# L298213.net
KiCad netlist of a schematic drawn in EAGLE
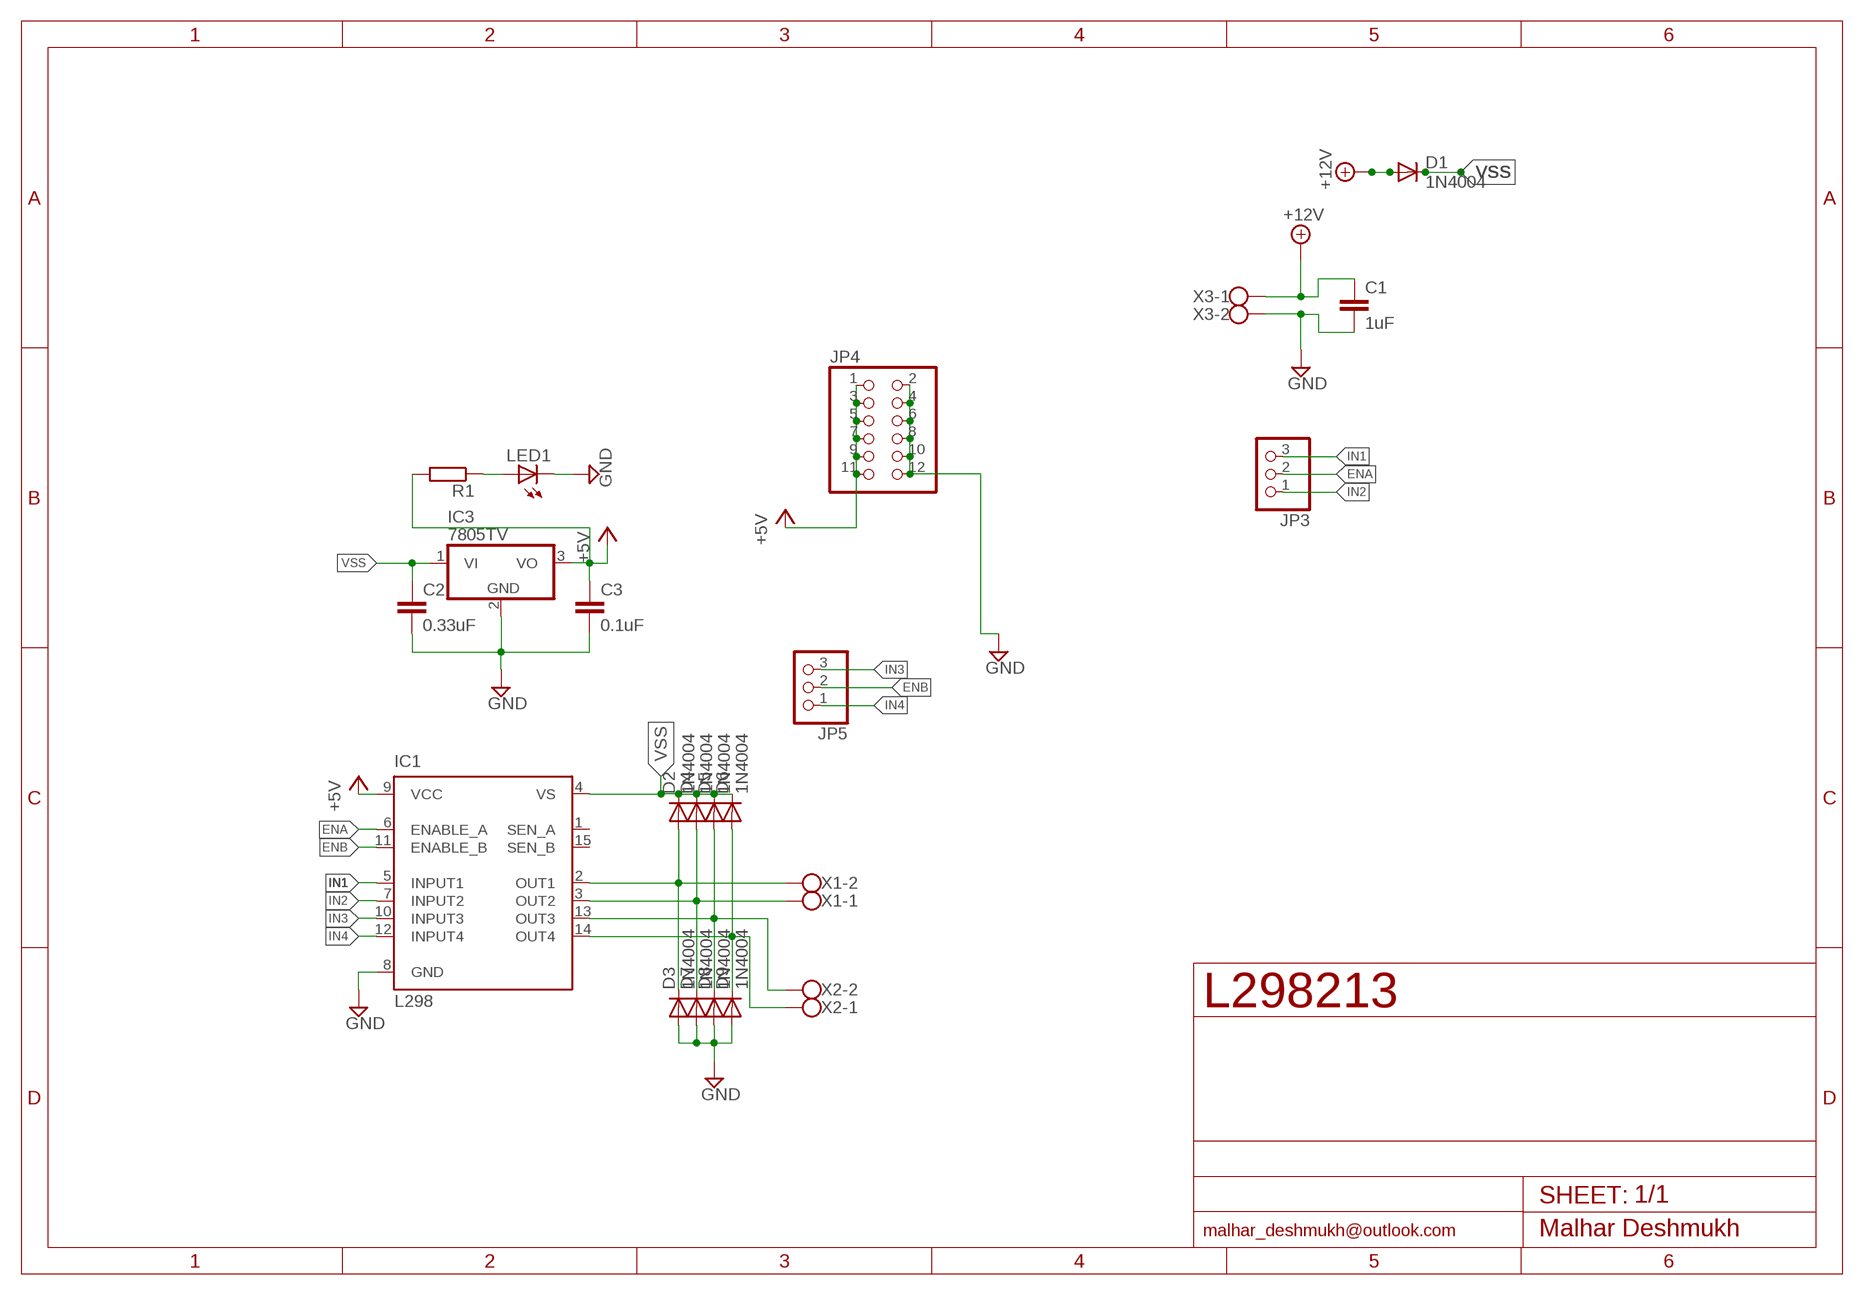
[diagram p0: schematic, sheet 1]

(export (version "E")
  (design (tool "Eeschema 10.0.6"))
  (components
    (comp (ref "C1")
      (value "1uF")
      (footprint "eagle-import:C050-024X044")
      (libsource (lib "eagle-import") (part "C-EU050-024X044"))
    )
    (comp (ref "C2")
      (value "0.33uF")
      (footprint "eagle-import:C050-024X044")
      (libsource (lib "eagle-import") (part "C-EU050-024X044"))
    )
    (comp (ref "C3")
      (value "0.1uF")
      (footprint "eagle-import:C050-024X044")
      (libsource (lib "eagle-import") (part "C-EU050-024X044"))
    )
    (comp (ref "D1")
      (value "1N4004")
      (footprint "eagle-import:DO41-10")
      (libsource (lib "eagle-import") (part "1N4004"))
    )
    (comp (ref "D2")
      (value "1N4004")
      (footprint "eagle-import:DO41-10")
      (libsource (lib "eagle-import") (part "1N4004"))
    )
    (comp (ref "D3")
      (value "1N4004")
      (footprint "eagle-import:DO41-10")
      (libsource (lib "eagle-import") (part "1N4004"))
    )
    (comp (ref "D4")
      (value "1N4004")
      (footprint "eagle-import:DO41-10")
      (libsource (lib "eagle-import") (part "1N4004"))
    )
    (comp (ref "D5")
      (value "1N4004")
      (footprint "eagle-import:DO41-10")
      (libsource (lib "eagle-import") (part "1N4004"))
    )
    (comp (ref "D6")
      (value "1N4004")
      (footprint "eagle-import:DO41-10")
      (libsource (lib "eagle-import") (part "1N4004"))
    )
    (comp (ref "D7")
      (value "1N4004")
      (footprint "eagle-import:DO41-10")
      (libsource (lib "eagle-import") (part "1N4004"))
    )
    (comp (ref "D8")
      (value "1N4004")
      (footprint "eagle-import:DO41-10")
      (libsource (lib "eagle-import") (part "1N4004"))
    )
    (comp (ref "D9")
      (value "1N4004")
      (footprint "eagle-import:DO41-10")
      (libsource (lib "eagle-import") (part "1N4004"))
    )
    (comp (ref "IC1")
      (value "L298")
      (footprint "eagle-import:MULTIWATT-15")
      (fields (field (name "MPN") "L298N"))
      (libsource (lib "eagle-import") (part "L298"))
    )
    (comp (ref "IC3")
      (value "7805TV")
      (footprint "eagle-import:TO220V")
      (libsource (lib "eagle-import") (part "78TV05"))
    )
    (comp (ref "JP3")
      (value "PINHD-1X3")
      (footprint "eagle-import:1X03")
      (libsource (lib "eagle-import") (part "PINHD-1X3"))
    )
    (comp (ref "JP4")
      (value "PINHD-2X6")
      (footprint "eagle-import:2X06")
      (libsource (lib "eagle-import") (part "PINHD-2X6"))
    )
    (comp (ref "JP5")
      (value "PINHD-1X3")
      (footprint "eagle-import:1X03")
      (libsource (lib "eagle-import") (part "PINHD-1X3"))
    )
    (comp (ref "LED1")
      (value "LED3MM")
      (footprint "eagle-import:LED3MM")
      (libsource (lib "eagle-import") (part "LED3MM"))
    )
    (comp (ref "R1")
      (value "R-EU_0207/5V")
      (footprint "eagle-import:0207_5V")
      (libsource (lib "eagle-import") (part "R-EU_0207/5V"))
    )
    (comp (ref "X1")
      (value "W237-102")
      (footprint "eagle-import:W237-102")
      (fields (field (name "MPN") "237-102"))
      (libsource (lib "eagle-import") (part "W237-102"))
    )
    (comp (ref "X2")
      (value "W237-102")
      (footprint "eagle-import:W237-102")
      (fields (field (name "MPN") "237-102"))
      (libsource (lib "eagle-import") (part "W237-102"))
    )
    (comp (ref "X3")
      (value "W237-102")
      (footprint "eagle-import:W237-102")
      (fields (field (name "MPN") "237-102"))
      (libsource (lib "eagle-import") (part "W237-102"))
    )
  )
  (nets
    (net (code "1") (name "+5V") (class "Default")
      (node (ref "C3") (pin "1") (pinfunction "1_1") (pintype "passive"))
      (node (ref "IC1") (pin "9") (pinfunction "VCC_9") (pintype "power_in"))
      (node (ref "IC3") (pin "3") (pinfunction "VO_3") (pintype "passive"))
      (node (ref "JP4") (pin "1") (pinfunction "1_1") (pintype "passive"))
      (node (ref "JP4") (pin "11") (pinfunction "11_11") (pintype "passive"))
      (node (ref "JP4") (pin "3") (pinfunction "3_3") (pintype "passive"))
      (node (ref "JP4") (pin "5") (pinfunction "5_5") (pintype "passive"))
      (node (ref "JP4") (pin "7") (pinfunction "7_7") (pintype "passive"))
      (node (ref "JP4") (pin "9") (pinfunction "9_9") (pintype "passive"))
      (node (ref "R1") (pin "2") (pinfunction "2_2") (pintype "passive"))
    )
    (net (code "2") (name "+12V") (class "Default")
      (node (ref "C1") (pin "1") (pinfunction "1_1") (pintype "passive"))
      (node (ref "D1") (pin "A") (pinfunction "A_A") (pintype "passive"))
      (node (ref "X3") (pin "1") (pinfunction "KL_1") (pintype "passive"))
    )
    (net (code "3") (name "ENA") (class "Default")
      (node (ref "IC1") (pin "6") (pinfunction "ENABLE_A_6") (pintype "input"))
      (node (ref "JP3") (pin "2") (pinfunction "2_2") (pintype "passive"))
    )
    (net (code "4") (name "ENB") (class "Default")
      (node (ref "IC1") (pin "11") (pinfunction "ENABLE_B_11") (pintype "input"))
      (node (ref "JP5") (pin "2") (pinfunction "2_2") (pintype "passive"))
    )
    (net (code "5") (name "GND") (class "Default")
      (node (ref "C1") (pin "2") (pinfunction "2_2") (pintype "passive"))
      (node (ref "C2") (pin "2") (pinfunction "2_2") (pintype "passive"))
      (node (ref "C3") (pin "2") (pinfunction "2_2") (pintype "passive"))
      (node (ref "D3") (pin "A") (pinfunction "A_A") (pintype "passive"))
      (node (ref "D7") (pin "A") (pinfunction "A_A") (pintype "passive"))
      (node (ref "D8") (pin "A") (pinfunction "A_A") (pintype "passive"))
      (node (ref "D9") (pin "A") (pinfunction "A_A") (pintype "passive"))
      (node (ref "IC1") (pin "8") (pinfunction "GND_8") (pintype "power_in"))
      (node (ref "IC3") (pin "2") (pinfunction "GND_2") (pintype "passive"))
      (node (ref "JP4") (pin "10") (pinfunction "10_10") (pintype "passive"))
      (node (ref "JP4") (pin "12") (pinfunction "12_12") (pintype "passive"))
      (node (ref "JP4") (pin "2") (pinfunction "2_2") (pintype "passive"))
      (node (ref "JP4") (pin "4") (pinfunction "4_4") (pintype "passive"))
      (node (ref "JP4") (pin "6") (pinfunction "6_6") (pintype "passive"))
      (node (ref "JP4") (pin "8") (pinfunction "8_8") (pintype "passive"))
      (node (ref "LED1") (pin "K") (pinfunction "C_K") (pintype "passive"))
      (node (ref "X3") (pin "2") (pinfunction "KL_2") (pintype "passive"))
    )
    (net (code "6") (name "IN1") (class "Default")
      (node (ref "IC1") (pin "5") (pinfunction "INPUT1_5") (pintype "input"))
      (node (ref "JP3") (pin "3") (pinfunction "3_3") (pintype "passive"))
    )
    (net (code "7") (name "IN2") (class "Default")
      (node (ref "IC1") (pin "7") (pinfunction "INPUT2_7") (pintype "input"))
      (node (ref "JP3") (pin "1") (pinfunction "1_1") (pintype "passive"))
    )
    (net (code "8") (name "IN3") (class "Default")
      (node (ref "IC1") (pin "10") (pinfunction "INPUT3_10") (pintype "input"))
      (node (ref "JP5") (pin "3") (pinfunction "3_3") (pintype "passive"))
    )
    (net (code "9") (name "IN4") (class "Default")
      (node (ref "IC1") (pin "12") (pinfunction "INPUT4_12") (pintype "input"))
      (node (ref "JP5") (pin "1") (pinfunction "1_1") (pintype "passive"))
    )
    (net (code "10") (name "Net-(IC1-OUT1)") (class "Default")
      (node (ref "D2") (pin "A") (pinfunction "A_A") (pintype "passive"))
      (node (ref "D3") (pin "C") (pinfunction "C_C") (pintype "passive"))
      (node (ref "IC1") (pin "2") (pinfunction "OUT1_2") (pintype "output"))
      (node (ref "X1") (pin "2") (pinfunction "KL_2") (pintype "passive"))
    )
    (net (code "11") (name "Net-(IC1-OUT2)") (class "Default")
      (node (ref "D4") (pin "A") (pinfunction "A_A") (pintype "passive"))
      (node (ref "D7") (pin "C") (pinfunction "C_C") (pintype "passive"))
      (node (ref "IC1") (pin "3") (pinfunction "OUT2_3") (pintype "output"))
      (node (ref "X1") (pin "1") (pinfunction "KL_1") (pintype "passive"))
    )
    (net (code "12") (name "Net-(IC1-OUT3)") (class "Default")
      (node (ref "D5") (pin "A") (pinfunction "A_A") (pintype "passive"))
      (node (ref "D8") (pin "C") (pinfunction "C_C") (pintype "passive"))
      (node (ref "IC1") (pin "13") (pinfunction "OUT3_13") (pintype "output"))
      (node (ref "X2") (pin "2") (pinfunction "KL_2") (pintype "passive"))
    )
    (net (code "13") (name "Net-(IC1-OUT4)") (class "Default")
      (node (ref "D6") (pin "A") (pinfunction "A_A") (pintype "passive"))
      (node (ref "D9") (pin "C") (pinfunction "C_C") (pintype "passive"))
      (node (ref "IC1") (pin "14") (pinfunction "OUT4_14") (pintype "output"))
      (node (ref "X2") (pin "1") (pinfunction "KL_1") (pintype "passive"))
    )
    (net (code "14") (name "Net-(LED1-PadA)") (class "Default")
      (node (ref "LED1") (pin "A") (pinfunction "A_A") (pintype "passive"))
      (node (ref "R1") (pin "1") (pinfunction "1_1") (pintype "passive"))
    )
    (net (code "15") (name "VSS") (class "Default")
      (node (ref "C2") (pin "1") (pinfunction "1_1") (pintype "passive"))
      (node (ref "D1") (pin "C") (pinfunction "C_C") (pintype "passive"))
      (node (ref "D2") (pin "C") (pinfunction "C_C") (pintype "passive"))
      (node (ref "D4") (pin "C") (pinfunction "C_C") (pintype "passive"))
      (node (ref "D5") (pin "C") (pinfunction "C_C") (pintype "passive"))
      (node (ref "D6") (pin "C") (pinfunction "C_C") (pintype "passive"))
      (node (ref "IC1") (pin "4") (pinfunction "VS_4") (pintype "power_in"))
      (node (ref "IC3") (pin "1") (pinfunction "VI_1") (pintype "input"))
    )
    (net (code "16") (name "unconnected-(IC1-SEN_A-Pad1)") (class "Default")
      (node (ref "IC1") (pin "1") (pinfunction "SEN_A_1") (pintype "input"))
    )
    (net (code "17") (name "unconnected-(IC1-SEN_B-Pad15)") (class "Default")
      (node (ref "IC1") (pin "15") (pinfunction "SEN_B_15") (pintype "input"))
    )
  )
)
